# CommandeMoteurs.net
KiCad netlist of a schematic drawn in EAGLE
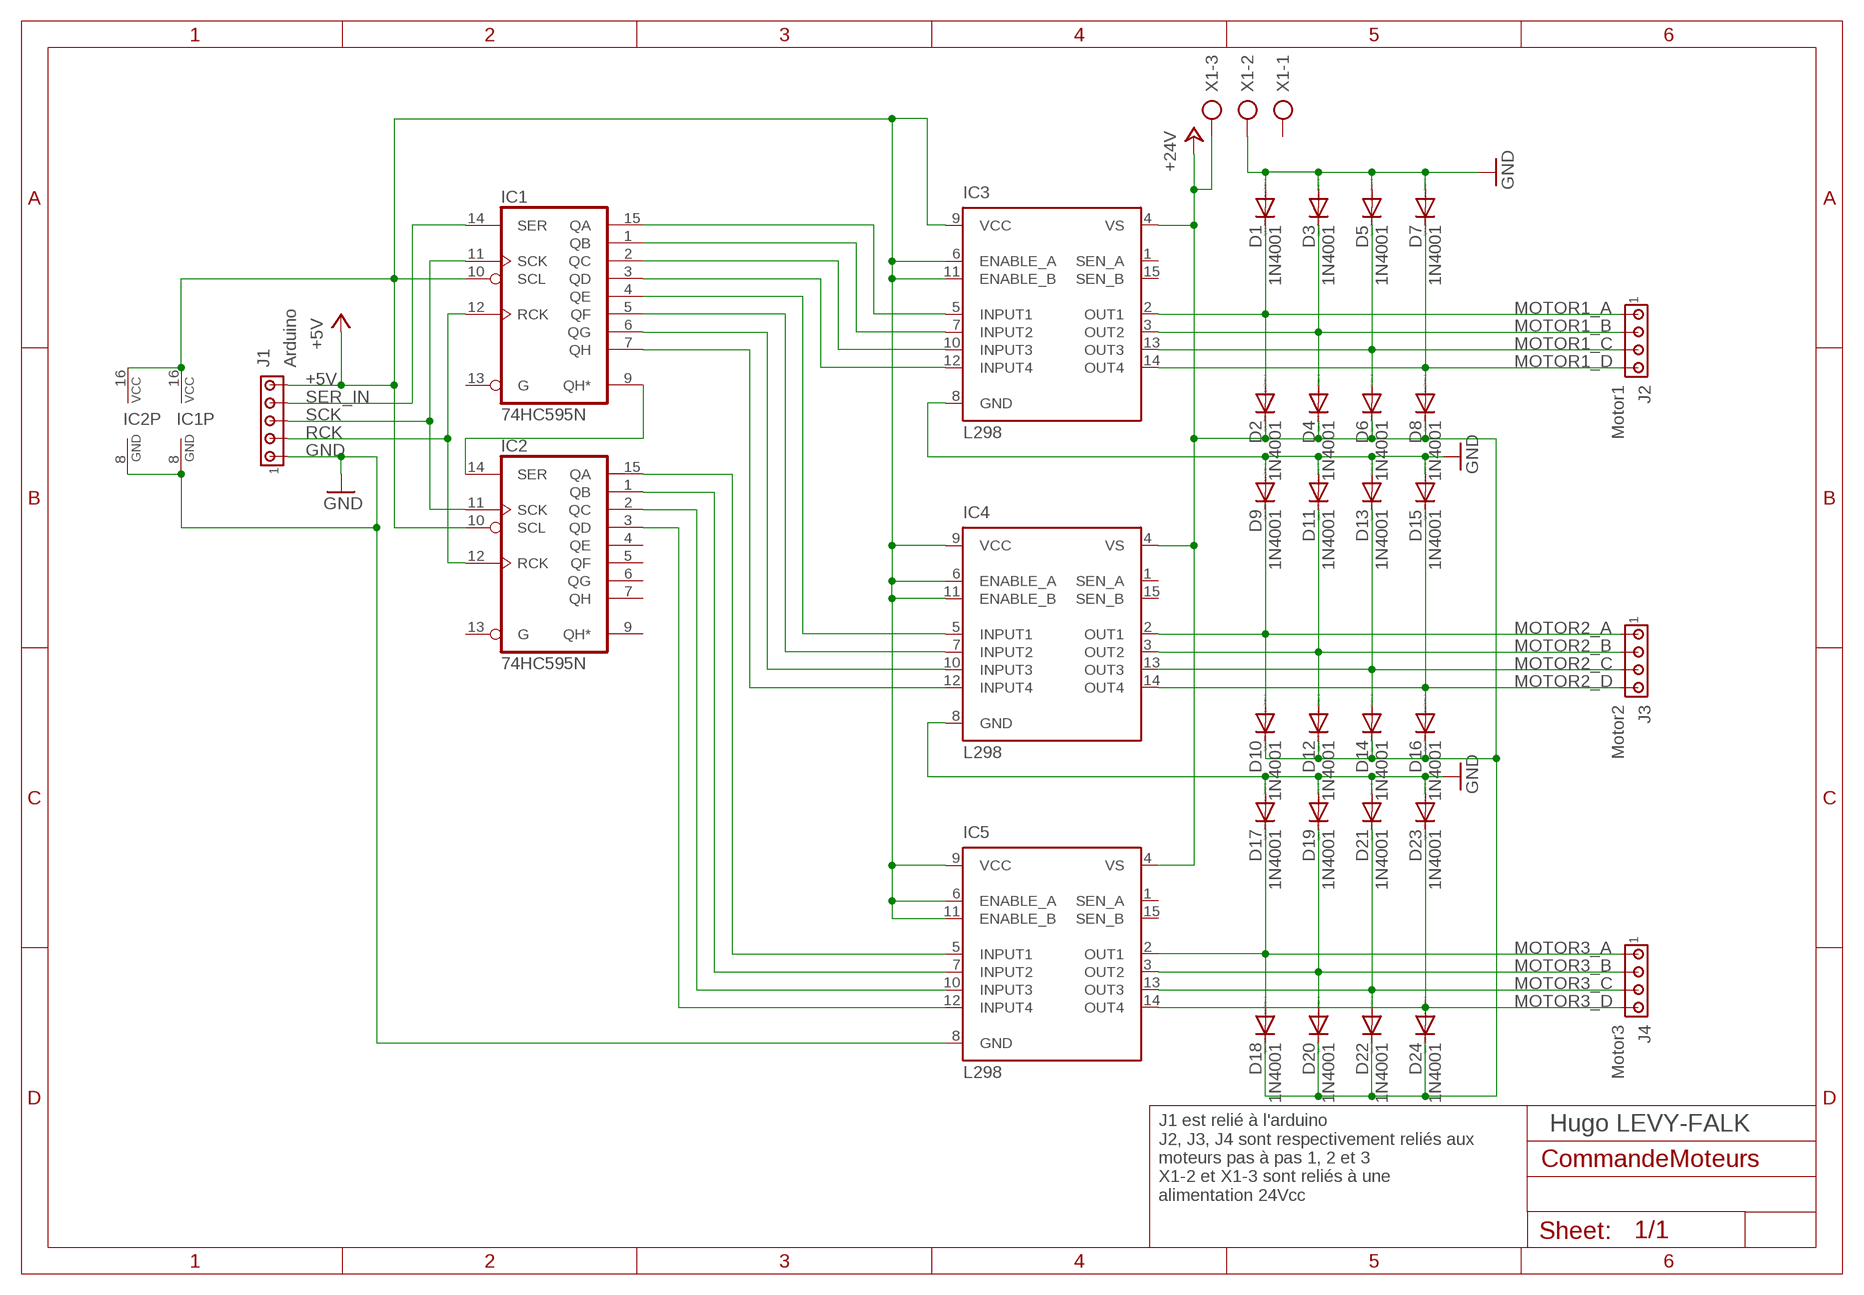
[diagram p0: schematic, sheet 1]

(export (version "E")
  (design (tool "Eeschema 10.0.6"))
  (components
    (comp (ref "D1")
      (value "1N4001")
      (footprint "eagle-import:DO35-10")
      (libsource (lib "eagle-import") (part "DIODE-DO35-10"))
    )
    (comp (ref "D2")
      (value "1N4001")
      (footprint "eagle-import:DO35-10")
      (libsource (lib "eagle-import") (part "DIODE-DO35-10"))
    )
    (comp (ref "D3")
      (value "1N4001")
      (footprint "eagle-import:DO35-10")
      (libsource (lib "eagle-import") (part "DIODE-DO35-10"))
    )
    (comp (ref "D4")
      (value "1N4001")
      (footprint "eagle-import:DO35-10")
      (libsource (lib "eagle-import") (part "DIODE-DO35-10"))
    )
    (comp (ref "D5")
      (value "1N4001")
      (footprint "eagle-import:DO35-10")
      (libsource (lib "eagle-import") (part "DIODE-DO35-10"))
    )
    (comp (ref "D6")
      (value "1N4001")
      (footprint "eagle-import:DO35-10")
      (libsource (lib "eagle-import") (part "DIODE-DO35-10"))
    )
    (comp (ref "D7")
      (value "1N4001")
      (footprint "eagle-import:DO35-10")
      (libsource (lib "eagle-import") (part "DIODE-DO35-10"))
    )
    (comp (ref "D8")
      (value "1N4001")
      (footprint "eagle-import:DO35-10")
      (libsource (lib "eagle-import") (part "DIODE-DO35-10"))
    )
    (comp (ref "D9")
      (value "1N4001")
      (footprint "eagle-import:DO35-10")
      (libsource (lib "eagle-import") (part "DIODE-DO35-10"))
    )
    (comp (ref "D10")
      (value "1N4001")
      (footprint "eagle-import:DO35-10")
      (libsource (lib "eagle-import") (part "DIODE-DO35-10"))
    )
    (comp (ref "D11")
      (value "1N4001")
      (footprint "eagle-import:DO35-10")
      (libsource (lib "eagle-import") (part "DIODE-DO35-10"))
    )
    (comp (ref "D12")
      (value "1N4001")
      (footprint "eagle-import:DO35-10")
      (libsource (lib "eagle-import") (part "DIODE-DO35-10"))
    )
    (comp (ref "D13")
      (value "1N4001")
      (footprint "eagle-import:DO35-10")
      (libsource (lib "eagle-import") (part "DIODE-DO35-10"))
    )
    (comp (ref "D14")
      (value "1N4001")
      (footprint "eagle-import:DO35-10")
      (libsource (lib "eagle-import") (part "DIODE-DO35-10"))
    )
    (comp (ref "D15")
      (value "1N4001")
      (footprint "eagle-import:DO35-10")
      (libsource (lib "eagle-import") (part "DIODE-DO35-10"))
    )
    (comp (ref "D16")
      (value "1N4001")
      (footprint "eagle-import:DO35-10")
      (libsource (lib "eagle-import") (part "DIODE-DO35-10"))
    )
    (comp (ref "D17")
      (value "1N4001")
      (footprint "eagle-import:DO35-10")
      (libsource (lib "eagle-import") (part "DIODE-DO35-10"))
    )
    (comp (ref "D18")
      (value "1N4001")
      (footprint "eagle-import:DO35-10")
      (libsource (lib "eagle-import") (part "DIODE-DO35-10"))
    )
    (comp (ref "D19")
      (value "1N4001")
      (footprint "eagle-import:DO35-10")
      (libsource (lib "eagle-import") (part "DIODE-DO35-10"))
    )
    (comp (ref "D20")
      (value "1N4001")
      (footprint "eagle-import:DO35-10")
      (libsource (lib "eagle-import") (part "DIODE-DO35-10"))
    )
    (comp (ref "D21")
      (value "1N4001")
      (footprint "eagle-import:DO35-10")
      (libsource (lib "eagle-import") (part "DIODE-DO35-10"))
    )
    (comp (ref "D22")
      (value "1N4001")
      (footprint "eagle-import:DO35-10")
      (libsource (lib "eagle-import") (part "DIODE-DO35-10"))
    )
    (comp (ref "D23")
      (value "1N4001")
      (footprint "eagle-import:DO35-10")
      (libsource (lib "eagle-import") (part "DIODE-DO35-10"))
    )
    (comp (ref "D24")
      (value "1N4001")
      (footprint "eagle-import:DO35-10")
      (libsource (lib "eagle-import") (part "DIODE-DO35-10"))
    )
    (comp (ref "IC1")
      (value "74HC595N")
      (footprint "eagle-import:DIL16")
      (libsource (lib "eagle-import") (part "74595NHC"))
    )
    (comp (ref "IC2")
      (value "74HC595N")
      (footprint "eagle-import:DIL16")
      (libsource (lib "eagle-import") (part "74595NHC"))
    )
    (comp (ref "IC3")
      (value "L298")
      (footprint "eagle-import:MULTIWATT-15")
      (fields (field (name "MPN") "L298N"))
      (libsource (lib "eagle-import") (part "L298"))
    )
    (comp (ref "IC4")
      (value "L298")
      (footprint "eagle-import:MULTIWATT-15")
      (fields (field (name "MPN") "L298N"))
      (libsource (lib "eagle-import") (part "L298"))
    )
    (comp (ref "IC5")
      (value "L298")
      (footprint "eagle-import:MULTIWATT-15")
      (fields (field (name "MPN") "L298N"))
      (libsource (lib "eagle-import") (part "L298"))
    )
    (comp (ref "J1")
      (value "Arduino")
      (footprint "eagle-import:10X05MTA")
      (libsource (lib "eagle-import") (part "MTA05-100"))
    )
    (comp (ref "J2")
      (value "Motor1")
      (footprint "eagle-import:10X04MTA")
      (libsource (lib "eagle-import") (part "MTA04-100"))
    )
    (comp (ref "J3")
      (value "Motor2")
      (footprint "eagle-import:10X04MTA")
      (libsource (lib "eagle-import") (part "MTA04-100"))
    )
    (comp (ref "J4")
      (value "Motor3")
      (footprint "eagle-import:10X04MTA")
      (libsource (lib "eagle-import") (part "MTA04-100"))
    )
    (comp (ref "X1")
      (value "AK500/3")
      (footprint "eagle-import:AK500_3")
      (libsource (lib "eagle-import") (part "AK500/3"))
    )
  )
  (nets
    (net (code "1") (name "+5V") (class "Default")
      (node (ref "IC1") (pin "10") (pinfunction "SCL_10") (pintype "input"))
      (node (ref "IC1") (pin "16") (pinfunction "VCC_16") (pintype "power_in"))
      (node (ref "IC2") (pin "10") (pinfunction "SCL_10") (pintype "input"))
      (node (ref "IC2") (pin "16") (pinfunction "VCC_16") (pintype "power_in"))
      (node (ref "IC3") (pin "11") (pinfunction "ENABLE_B_11") (pintype "input"))
      (node (ref "IC3") (pin "6") (pinfunction "ENABLE_A_6") (pintype "input"))
      (node (ref "IC3") (pin "9") (pinfunction "VCC_9") (pintype "power_in"))
      (node (ref "IC4") (pin "11") (pinfunction "ENABLE_B_11") (pintype "input"))
      (node (ref "IC4") (pin "6") (pinfunction "ENABLE_A_6") (pintype "input"))
      (node (ref "IC4") (pin "9") (pinfunction "VCC_9") (pintype "power_in"))
      (node (ref "IC5") (pin "11") (pinfunction "ENABLE_B_11") (pintype "input"))
      (node (ref "IC5") (pin "6") (pinfunction "ENABLE_A_6") (pintype "input"))
      (node (ref "IC5") (pin "9") (pinfunction "VCC_9") (pintype "power_in"))
      (node (ref "J1") (pin "5") (pinfunction "5_5") (pintype "passive"))
    )
    (net (code "2") (name "+24V") (class "Default")
      (node (ref "D10") (pin "C") (pinfunction "C_C") (pintype "passive"))
      (node (ref "D12") (pin "C") (pinfunction "C_C") (pintype "passive"))
      (node (ref "D14") (pin "C") (pinfunction "C_C") (pintype "passive"))
      (node (ref "D16") (pin "C") (pinfunction "C_C") (pintype "passive"))
      (node (ref "D18") (pin "C") (pinfunction "C_C") (pintype "passive"))
      (node (ref "D2") (pin "C") (pinfunction "C_C") (pintype "passive"))
      (node (ref "D20") (pin "C") (pinfunction "C_C") (pintype "passive"))
      (node (ref "D22") (pin "C") (pinfunction "C_C") (pintype "passive"))
      (node (ref "D24") (pin "C") (pinfunction "C_C") (pintype "passive"))
      (node (ref "D4") (pin "C") (pinfunction "C_C") (pintype "passive"))
      (node (ref "D6") (pin "C") (pinfunction "C_C") (pintype "passive"))
      (node (ref "D8") (pin "C") (pinfunction "C_C") (pintype "passive"))
      (node (ref "IC3") (pin "4") (pinfunction "VS_4") (pintype "power_in"))
      (node (ref "IC4") (pin "4") (pinfunction "VS_4") (pintype "power_in"))
      (node (ref "IC5") (pin "4") (pinfunction "VS_4") (pintype "power_in"))
      (node (ref "X1") (pin "3") (pinfunction "KL_3") (pintype "passive"))
    )
    (net (code "3") (name "/MOTOR1_A") (class "Default")
      (node (ref "D1") (pin "C") (pinfunction "C_C") (pintype "passive"))
      (node (ref "D2") (pin "A") (pinfunction "A_A") (pintype "passive"))
      (node (ref "IC3") (pin "2") (pinfunction "OUT1_2") (pintype "output"))
      (node (ref "J2") (pin "1") (pinfunction "1_1") (pintype "passive"))
    )
    (net (code "4") (name "/MOTOR1_B") (class "Default")
      (node (ref "D3") (pin "C") (pinfunction "C_C") (pintype "passive"))
      (node (ref "D4") (pin "A") (pinfunction "A_A") (pintype "passive"))
      (node (ref "IC3") (pin "3") (pinfunction "OUT2_3") (pintype "output"))
      (node (ref "J2") (pin "2") (pinfunction "2_2") (pintype "passive"))
    )
    (net (code "5") (name "/MOTOR1_C") (class "Default")
      (node (ref "D5") (pin "C") (pinfunction "C_C") (pintype "passive"))
      (node (ref "D6") (pin "A") (pinfunction "A_A") (pintype "passive"))
      (node (ref "IC3") (pin "13") (pinfunction "OUT3_13") (pintype "output"))
      (node (ref "J2") (pin "3") (pinfunction "3_3") (pintype "passive"))
    )
    (net (code "6") (name "/MOTOR1_D") (class "Default")
      (node (ref "D7") (pin "C") (pinfunction "C_C") (pintype "passive"))
      (node (ref "D8") (pin "A") (pinfunction "A_A") (pintype "passive"))
      (node (ref "IC3") (pin "14") (pinfunction "OUT4_14") (pintype "output"))
      (node (ref "J2") (pin "4") (pinfunction "4_4") (pintype "passive"))
    )
    (net (code "7") (name "/MOTOR2_A") (class "Default")
      (node (ref "D10") (pin "A") (pinfunction "A_A") (pintype "passive"))
      (node (ref "D9") (pin "C") (pinfunction "C_C") (pintype "passive"))
      (node (ref "IC4") (pin "2") (pinfunction "OUT1_2") (pintype "output"))
      (node (ref "J3") (pin "1") (pinfunction "1_1") (pintype "passive"))
    )
    (net (code "8") (name "/MOTOR2_B") (class "Default")
      (node (ref "D11") (pin "C") (pinfunction "C_C") (pintype "passive"))
      (node (ref "D12") (pin "A") (pinfunction "A_A") (pintype "passive"))
      (node (ref "IC4") (pin "3") (pinfunction "OUT2_3") (pintype "output"))
      (node (ref "J3") (pin "2") (pinfunction "2_2") (pintype "passive"))
    )
    (net (code "9") (name "/MOTOR2_C") (class "Default")
      (node (ref "D13") (pin "C") (pinfunction "C_C") (pintype "passive"))
      (node (ref "D14") (pin "A") (pinfunction "A_A") (pintype "passive"))
      (node (ref "IC4") (pin "13") (pinfunction "OUT3_13") (pintype "output"))
      (node (ref "J3") (pin "3") (pinfunction "3_3") (pintype "passive"))
    )
    (net (code "10") (name "/MOTOR2_D") (class "Default")
      (node (ref "D15") (pin "C") (pinfunction "C_C") (pintype "passive"))
      (node (ref "D16") (pin "A") (pinfunction "A_A") (pintype "passive"))
      (node (ref "IC4") (pin "14") (pinfunction "OUT4_14") (pintype "output"))
      (node (ref "J3") (pin "4") (pinfunction "4_4") (pintype "passive"))
    )
    (net (code "11") (name "/MOTOR3_A") (class "Default")
      (node (ref "D17") (pin "C") (pinfunction "C_C") (pintype "passive"))
      (node (ref "D18") (pin "A") (pinfunction "A_A") (pintype "passive"))
      (node (ref "IC5") (pin "2") (pinfunction "OUT1_2") (pintype "output"))
      (node (ref "J4") (pin "1") (pinfunction "1_1") (pintype "passive"))
    )
    (net (code "12") (name "/MOTOR3_B") (class "Default")
      (node (ref "D19") (pin "C") (pinfunction "C_C") (pintype "passive"))
      (node (ref "D20") (pin "A") (pinfunction "A_A") (pintype "passive"))
      (node (ref "IC5") (pin "3") (pinfunction "OUT2_3") (pintype "output"))
      (node (ref "J4") (pin "2") (pinfunction "2_2") (pintype "passive"))
    )
    (net (code "13") (name "/MOTOR3_C") (class "Default")
      (node (ref "D21") (pin "C") (pinfunction "C_C") (pintype "passive"))
      (node (ref "D22") (pin "A") (pinfunction "A_A") (pintype "passive"))
      (node (ref "IC5") (pin "13") (pinfunction "OUT3_13") (pintype "output"))
      (node (ref "J4") (pin "3") (pinfunction "3_3") (pintype "passive"))
    )
    (net (code "14") (name "/MOTOR3_D") (class "Default")
      (node (ref "D23") (pin "C") (pinfunction "C_C") (pintype "passive"))
      (node (ref "D24") (pin "A") (pinfunction "A_A") (pintype "passive"))
      (node (ref "IC5") (pin "14") (pinfunction "OUT4_14") (pintype "output"))
      (node (ref "J4") (pin "4") (pinfunction "4_4") (pintype "passive"))
    )
    (net (code "15") (name "/RCK") (class "Default")
      (node (ref "IC1") (pin "12") (pinfunction "RCK_12") (pintype "input"))
      (node (ref "IC2") (pin "12") (pinfunction "RCK_12") (pintype "input"))
      (node (ref "J1") (pin "2") (pinfunction "2_2") (pintype "passive"))
    )
    (net (code "16") (name "/SCK") (class "Default")
      (node (ref "IC1") (pin "11") (pinfunction "SCK_11") (pintype "input"))
      (node (ref "IC2") (pin "11") (pinfunction "SCK_11") (pintype "input"))
      (node (ref "J1") (pin "3") (pinfunction "3_3") (pintype "passive"))
    )
    (net (code "17") (name "/SER_IN") (class "Default")
      (node (ref "IC1") (pin "14") (pinfunction "SER_14") (pintype "input"))
      (node (ref "J1") (pin "4") (pinfunction "4_4") (pintype "passive"))
    )
    (net (code "18") (name "GND") (class "Default")
      (node (ref "D1") (pin "A") (pinfunction "A_A") (pintype "passive"))
      (node (ref "D11") (pin "A") (pinfunction "A_A") (pintype "passive"))
      (node (ref "D13") (pin "A") (pinfunction "A_A") (pintype "passive"))
      (node (ref "D15") (pin "A") (pinfunction "A_A") (pintype "passive"))
      (node (ref "D17") (pin "A") (pinfunction "A_A") (pintype "passive"))
      (node (ref "D19") (pin "A") (pinfunction "A_A") (pintype "passive"))
      (node (ref "D21") (pin "A") (pinfunction "A_A") (pintype "passive"))
      (node (ref "D23") (pin "A") (pinfunction "A_A") (pintype "passive"))
      (node (ref "D3") (pin "A") (pinfunction "A_A") (pintype "passive"))
      (node (ref "D5") (pin "A") (pinfunction "A_A") (pintype "passive"))
      (node (ref "D7") (pin "A") (pinfunction "A_A") (pintype "passive"))
      (node (ref "D9") (pin "A") (pinfunction "A_A") (pintype "passive"))
      (node (ref "IC1") (pin "8") (pinfunction "GND_8") (pintype "power_in"))
      (node (ref "IC2") (pin "8") (pinfunction "GND_8") (pintype "power_in"))
      (node (ref "IC3") (pin "8") (pinfunction "GND_8") (pintype "power_in"))
      (node (ref "IC4") (pin "8") (pinfunction "GND_8") (pintype "power_in"))
      (node (ref "IC5") (pin "8") (pinfunction "GND_8") (pintype "power_in"))
      (node (ref "J1") (pin "1") (pinfunction "1_1") (pintype "passive"))
      (node (ref "X1") (pin "2") (pinfunction "KL_2") (pintype "passive"))
    )
    (net (code "19") (name "Net-(IC1A-QA)") (class "Default")
      (node (ref "IC1") (pin "15") (pinfunction "QA_15") (pintype "tri_state"))
      (node (ref "IC3") (pin "5") (pinfunction "INPUT1_5") (pintype "input"))
    )
    (net (code "20") (name "Net-(IC1A-QB)") (class "Default")
      (node (ref "IC1") (pin "1") (pinfunction "QB_1") (pintype "tri_state"))
      (node (ref "IC3") (pin "7") (pinfunction "INPUT2_7") (pintype "input"))
    )
    (net (code "21") (name "Net-(IC1A-QC)") (class "Default")
      (node (ref "IC1") (pin "2") (pinfunction "QC_2") (pintype "tri_state"))
      (node (ref "IC3") (pin "10") (pinfunction "INPUT3_10") (pintype "input"))
    )
    (net (code "22") (name "Net-(IC1A-QD)") (class "Default")
      (node (ref "IC1") (pin "3") (pinfunction "QD_3") (pintype "tri_state"))
      (node (ref "IC3") (pin "12") (pinfunction "INPUT4_12") (pintype "input"))
    )
    (net (code "23") (name "Net-(IC1A-QE)") (class "Default")
      (node (ref "IC1") (pin "4") (pinfunction "QE_4") (pintype "tri_state"))
      (node (ref "IC4") (pin "5") (pinfunction "INPUT1_5") (pintype "input"))
    )
    (net (code "24") (name "Net-(IC1A-QF)") (class "Default")
      (node (ref "IC1") (pin "5") (pinfunction "QF_5") (pintype "tri_state"))
      (node (ref "IC4") (pin "7") (pinfunction "INPUT2_7") (pintype "input"))
    )
    (net (code "25") (name "Net-(IC1A-QG)") (class "Default")
      (node (ref "IC1") (pin "6") (pinfunction "QG_6") (pintype "tri_state"))
      (node (ref "IC4") (pin "10") (pinfunction "INPUT3_10") (pintype "input"))
    )
    (net (code "26") (name "Net-(IC1A-QH)") (class "Default")
      (node (ref "IC1") (pin "7") (pinfunction "QH_7") (pintype "tri_state"))
      (node (ref "IC4") (pin "12") (pinfunction "INPUT4_12") (pintype "input"))
    )
    (net (code "27") (name "Net-(IC1A-QH*)") (class "Default")
      (node (ref "IC1") (pin "9") (pinfunction "QH*_9") (pintype "tri_state"))
      (node (ref "IC2") (pin "14") (pinfunction "SER_14") (pintype "input"))
    )
    (net (code "28") (name "Net-(IC2A-QA)") (class "Default")
      (node (ref "IC2") (pin "15") (pinfunction "QA_15") (pintype "tri_state"))
      (node (ref "IC5") (pin "5") (pinfunction "INPUT1_5") (pintype "input"))
    )
    (net (code "29") (name "Net-(IC2A-QB)") (class "Default")
      (node (ref "IC2") (pin "1") (pinfunction "QB_1") (pintype "tri_state"))
      (node (ref "IC5") (pin "7") (pinfunction "INPUT2_7") (pintype "input"))
    )
    (net (code "30") (name "Net-(IC2A-QC)") (class "Default")
      (node (ref "IC2") (pin "2") (pinfunction "QC_2") (pintype "tri_state"))
      (node (ref "IC5") (pin "10") (pinfunction "INPUT3_10") (pintype "input"))
    )
    (net (code "31") (name "Net-(IC2A-QD)") (class "Default")
      (node (ref "IC2") (pin "3") (pinfunction "QD_3") (pintype "tri_state"))
      (node (ref "IC5") (pin "12") (pinfunction "INPUT4_12") (pintype "input"))
    )
    (net (code "32") (name "unconnected-(IC1A-G-Pad13)") (class "Default")
      (node (ref "IC1") (pin "13") (pinfunction "G_13") (pintype "input"))
    )
    (net (code "33") (name "unconnected-(IC2A-G-Pad13)") (class "Default")
      (node (ref "IC2") (pin "13") (pinfunction "G_13") (pintype "input"))
    )
    (net (code "34") (name "unconnected-(IC2A-QE-Pad4)") (class "Default")
      (node (ref "IC2") (pin "4") (pinfunction "QE_4") (pintype "tri_state"))
    )
    (net (code "35") (name "unconnected-(IC2A-QF-Pad5)") (class "Default")
      (node (ref "IC2") (pin "5") (pinfunction "QF_5") (pintype "tri_state"))
    )
    (net (code "36") (name "unconnected-(IC2A-QG-Pad6)") (class "Default")
      (node (ref "IC2") (pin "6") (pinfunction "QG_6") (pintype "tri_state"))
    )
    (net (code "37") (name "unconnected-(IC2A-QH*-Pad9)") (class "Default")
      (node (ref "IC2") (pin "9") (pinfunction "QH*_9") (pintype "tri_state"))
    )
    (net (code "38") (name "unconnected-(IC2A-QH-Pad7)") (class "Default")
      (node (ref "IC2") (pin "7") (pinfunction "QH_7") (pintype "tri_state"))
    )
    (net (code "39") (name "unconnected-(IC3-SEN_A-Pad1)") (class "Default")
      (node (ref "IC3") (pin "1") (pinfunction "SEN_A_1") (pintype "input"))
    )
    (net (code "40") (name "unconnected-(IC3-SEN_B-Pad15)") (class "Default")
      (node (ref "IC3") (pin "15") (pinfunction "SEN_B_15") (pintype "input"))
    )
    (net (code "41") (name "unconnected-(IC4-SEN_A-Pad1)") (class "Default")
      (node (ref "IC4") (pin "1") (pinfunction "SEN_A_1") (pintype "input"))
    )
    (net (code "42") (name "unconnected-(IC4-SEN_B-Pad15)") (class "Default")
      (node (ref "IC4") (pin "15") (pinfunction "SEN_B_15") (pintype "input"))
    )
    (net (code "43") (name "unconnected-(IC5-SEN_A-Pad1)") (class "Default")
      (node (ref "IC5") (pin "1") (pinfunction "SEN_A_1") (pintype "input"))
    )
    (net (code "44") (name "unconnected-(IC5-SEN_B-Pad15)") (class "Default")
      (node (ref "IC5") (pin "15") (pinfunction "SEN_B_15") (pintype "input"))
    )
    (net (code "45") (name "unconnected-(X1A-KL-Pad1)") (class "Default")
      (node (ref "X1") (pin "1") (pinfunction "KL_1") (pintype "passive"))
    )
  )
)
